# Connections.net
KiCad netlist of a schematic drawn in Altium Designer
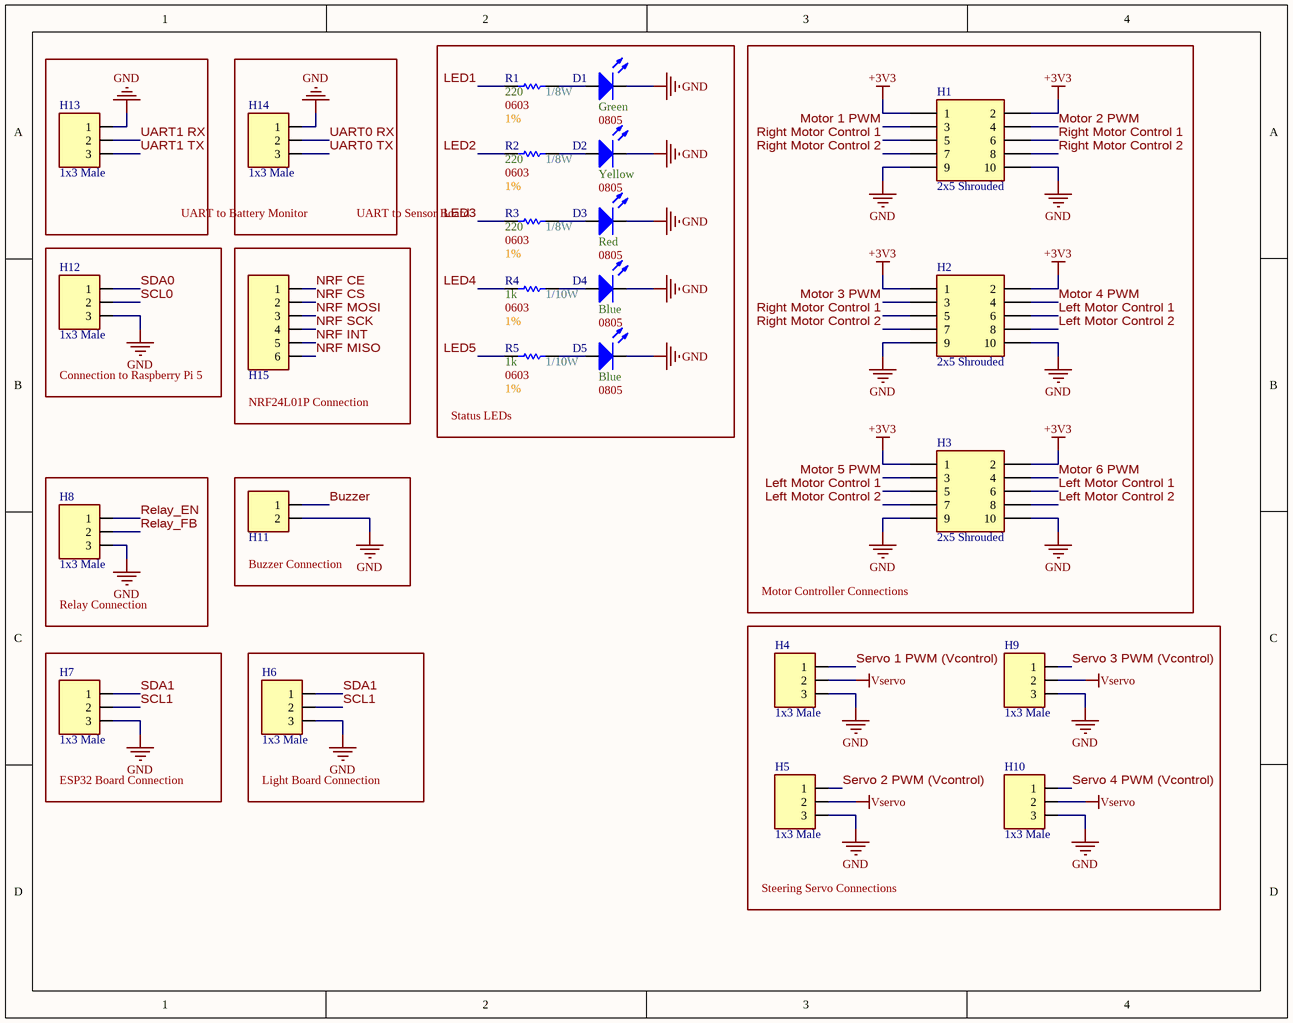
[diagram p0: Connections.SchDoc]

(export (version "E")
  (design (tool "Eeschema 10.0.6"))
  (components
    (comp (ref "D1")
      (value "[LED] SMD 0805 Green")
      (footprint "[LED] SMD 0805")
      (description "LG R971-KN-1-0-20-R18")
      (fields (field (name "COLOR") "Green") (field (name "SIZE PACKAGE") "0805"))
      (libsource (lib "LEDs") (part "[LED] SMD 0805 Green"))
    )
    (comp (ref "D2")
      (value "[LED] SMD 0805 Yellow")
      (footprint "[LED] SMD 0805")
      (description "LY R976-PS-36-0-20-R18")
      (fields (field (name "COLOR") "Yellow") (field (name "SIZE PACKAGE") "0805"))
      (libsource (lib "LEDs") (part "[LED] SMD 0805 Yellow"))
    )
    (comp (ref "D3")
      (value "[LED] SMD 0805 Red")
      (footprint "[LED] SMD 0805")
      (description "LS R976-NR-1-0-20-R18")
      (fields (field (name "COLOR") "Red") (field (name "SIZE PACKAGE") "0805"))
      (libsource (lib "LEDs") (part "[LED] SMD 0805 Red"))
    )
    (comp (ref "D4")
      (value "[LED] SMD 0805 Blue")
      (footprint "[LED] SMD 0805")
      (description "150080BS75000")
      (fields (field (name "COLOR") "Blue") (field (name "SIZE PACKAGE") "0805"))
      (libsource (lib "LEDs") (part "[LED] SMD 0805 Blue"))
    )
    (comp (ref "D5")
      (value "[LED] SMD 0805 Blue")
      (footprint "[LED] SMD 0805")
      (description "150080BS75000")
      (fields (field (name "COLOR") "Blue") (field (name "SIZE PACKAGE") "0805"))
      (libsource (lib "LEDs") (part "[LED] SMD 0805 Blue"))
    )
    (comp (ref "H1")
      (value "2x5 Shrouded")
      (footprint "[Header] Shrouded 2x5 Male")
      (description "BHR-10-VUA")
      (libsource (lib "RADM Connectors") (part "[Header] Shrouded 2x5 Male"))
    )
    (comp (ref "H2")
      (value "2x5 Shrouded")
      (footprint "[Header] Shrouded 2x5 Male")
      (description "BHR-10-VUA")
      (libsource (lib "RADM Connectors") (part "[Header] Shrouded 2x5 Male"))
    )
    (comp (ref "H3")
      (value "2x5 Shrouded")
      (footprint "[Header] Shrouded 2x5 Male")
      (description "BHR-10-VUA")
      (libsource (lib "RADM Connectors") (part "[Header] Shrouded 2x5 Male"))
    )
    (comp (ref "H4")
      (value "1x3 Male")
      (footprint "[Header] Shrouded 1x3 Male")
      (description "070543-0037\r\nMates with 005057-9403")
      (libsource (lib "RADM Connectors") (part "[Header] Shrouded 1x3 Male"))
    )
    (comp (ref "H5")
      (value "1x3 Male")
      (footprint "[Header] Shrouded 1x3 Male")
      (description "070543-0037\r\nMates with 005057-9403")
      (libsource (lib "RADM Connectors") (part "[Header] Shrouded 1x3 Male"))
    )
    (comp (ref "H6")
      (value "1x3 Male")
      (footprint "[Header] Shrouded 1x3 Male")
      (description "070543-0037\r\nMates with 005057-9403")
      (libsource (lib "RADM Connectors") (part "[Header] Shrouded 1x3 Male"))
    )
    (comp (ref "H7")
      (value "1x3 Male")
      (footprint "[Header] Shrouded 1x3 Male")
      (description "070543-0037\r\nMates with 005057-9403")
      (libsource (lib "RADM Connectors") (part "[Header] Shrouded 1x3 Male"))
    )
    (comp (ref "H8")
      (value "1x3 Male")
      (footprint "[Header] Shrouded 1x3 Male")
      (description "070543-0037\r\nMates with 005057-9403")
      (libsource (lib "RADM Connectors") (part "[Header] Shrouded 1x3 Male"))
    )
    (comp (ref "H9")
      (value "1x3 Male")
      (footprint "[Header] Shrouded 1x3 Male")
      (description "070543-0037\r\nMates with 005057-9403")
      (libsource (lib "RADM Connectors") (part "[Header] Shrouded 1x3 Male"))
    )
    (comp (ref "H10")
      (value "1x3 Male")
      (footprint "[Header] Shrouded 1x3 Male")
      (description "070543-0037\r\nMates with 005057-9403")
      (libsource (lib "RADM Connectors") (part "[Header] Shrouded 1x3 Male"))
    )
    (comp (ref "H11")
      (value "1x2 Male")
      (footprint "[Header] Shrouded 1x2 Male")
      (description "0705430036\r\nMates with 0050579402")
      (libsource (lib "RADM Connectors") (part "[Header] Shrouded 1x2 Male"))
    )
    (comp (ref "H12")
      (value "1x3 Male")
      (footprint "[Header] Shrouded 1x3 Male")
      (description "070543-0037\r\nMates with 005057-9403")
      (libsource (lib "RADM Connectors") (part "[Header] Shrouded 1x3 Male"))
    )
    (comp (ref "H13")
      (value "1x3 Male")
      (footprint "[Header] Shrouded 1x3 Male")
      (description "070543-0037\r\nMates with 005057-9403")
      (libsource (lib "RADM Connectors") (part "[Header] Shrouded 1x3 Male"))
    )
    (comp (ref "H14")
      (value "1x3 Male")
      (footprint "[Header] Shrouded 1x3 Male")
      (description "070543-0037\r\nMates with 005057-9403")
      (libsource (lib "RADM Connectors") (part "[Header] Shrouded 1x3 Male"))
    )
    (comp (ref "H15")
      (value "[Header] Shrouded 1x6 Male")
      (footprint "[Header] Shrouded 1x6 Male")
      (description "0705430005\r\nMates with 0050579406")
      (libsource (lib "RADM Connectors") (part "[Header] Shrouded 1x6 Male"))
    )
    (comp (ref "R1")
      (value "[220] SMD 0603 1% 1/10W")
      (footprint "[Res] SMD 0603")
      (description "CRGCQ0805F220R")
      (fields
        (field (name "WATTAGE") "1/8W")
        (field (name "TOLERANCE") "1%")
        (field (name "RESISTANCE") "220")
        (field (name "SIZE PACKAGE") "0603")
      )
      (libsource (lib "Resistors") (part "[220] SMD 0603 1% 1/10W"))
    )
    (comp (ref "R2")
      (value "[220] SMD 0603 1% 1/10W")
      (footprint "[Res] SMD 0603")
      (description "CRGCQ0805F220R")
      (fields
        (field (name "WATTAGE") "1/8W")
        (field (name "TOLERANCE") "1%")
        (field (name "RESISTANCE") "220")
        (field (name "SIZE PACKAGE") "0603")
      )
      (libsource (lib "Resistors") (part "[220] SMD 0603 1% 1/10W"))
    )
    (comp (ref "R3")
      (value "[220] SMD 0603 1% 1/10W")
      (footprint "[Res] SMD 0603")
      (description "CRGCQ0805F220R")
      (fields
        (field (name "WATTAGE") "1/8W")
        (field (name "TOLERANCE") "1%")
        (field (name "RESISTANCE") "220")
        (field (name "SIZE PACKAGE") "0603")
      )
      (libsource (lib "Resistors") (part "[220] SMD 0603 1% 1/10W"))
    )
    (comp (ref "R4")
      (value "[1k] SMD 0603 1% 1/10W")
      (footprint "[Res] SMD 0603")
      (description "RMCF0603FT1K00")
      (fields
        (field (name "WATTAGE") "1/10W")
        (field (name "TOLERANCE") "1%")
        (field (name "RESISTANCE") "1k")
        (field (name "SIZE PACKAGE") "0603")
      )
      (libsource (lib "Resistors") (part "[1k] SMD 0603 1% 1/10W"))
    )
    (comp (ref "R5")
      (value "[1k] SMD 0603 1% 1/10W")
      (footprint "[Res] SMD 0603")
      (description "RMCF0603FT1K00")
      (fields
        (field (name "WATTAGE") "1/10W")
        (field (name "TOLERANCE") "1%")
        (field (name "RESISTANCE") "1k")
        (field (name "SIZE PACKAGE") "0603")
      )
      (libsource (lib "Resistors") (part "[1k] SMD 0603 1% 1/10W"))
    )
  )
  (nets
    (net (code "1") (name "+3V3") (class "Default")
      (node (ref "H1") (pin "1") (pinfunction "1_1") (pintype "passive"))
      (node (ref "H1") (pin "2") (pinfunction "2_2") (pintype "passive"))
      (node (ref "H2") (pin "1") (pinfunction "1_1") (pintype "passive"))
      (node (ref "H2") (pin "2") (pinfunction "2_2") (pintype "passive"))
      (node (ref "H3") (pin "1") (pinfunction "1_1") (pintype "passive"))
      (node (ref "H3") (pin "2") (pinfunction "2_2") (pintype "passive"))
    )
    (net (code "2") (name "/Buzzer") (class "Default")
      (node (ref "H11") (pin "1") (pinfunction "1_1") (pintype "passive"))
    )
    (net (code "3") (name "/LED1") (class "Default")
      (node (ref "R1") (pin "1") (pinfunction "1_1") (pintype "passive"))
    )
    (net (code "4") (name "/LED2") (class "Default")
      (node (ref "R2") (pin "1") (pinfunction "1_1") (pintype "passive"))
    )
    (net (code "5") (name "/LED3") (class "Default")
      (node (ref "R3") (pin "1") (pinfunction "1_1") (pintype "passive"))
    )
    (net (code "6") (name "/LED4") (class "Default")
      (node (ref "R4") (pin "1") (pinfunction "1_1") (pintype "passive"))
    )
    (net (code "7") (name "/LED5") (class "Default")
      (node (ref "R5") (pin "1") (pinfunction "1_1") (pintype "passive"))
    )
    (net (code "8") (name "/Left Motor Control 1") (class "Default")
      (node (ref "H2") (pin "6") (pinfunction "6_6") (pintype "passive"))
      (node (ref "H3") (pin "5") (pinfunction "5_5") (pintype "passive"))
      (node (ref "H3") (pin "6") (pinfunction "6_6") (pintype "passive"))
    )
    (net (code "9") (name "/Left Motor Control 2") (class "Default")
      (node (ref "H2") (pin "8") (pinfunction "8_8") (pintype "passive"))
      (node (ref "H3") (pin "7") (pinfunction "7_7") (pintype "passive"))
      (node (ref "H3") (pin "8") (pinfunction "8_8") (pintype "passive"))
    )
    (net (code "10") (name "/Motor 1 PWM") (class "Default")
      (node (ref "H1") (pin "3") (pinfunction "3_3") (pintype "passive"))
    )
    (net (code "11") (name "/Motor 2 PWM") (class "Default")
      (node (ref "H1") (pin "4") (pinfunction "4_4") (pintype "passive"))
    )
    (net (code "12") (name "/Motor 3 PWM") (class "Default")
      (node (ref "H2") (pin "3") (pinfunction "3_3") (pintype "passive"))
    )
    (net (code "13") (name "/Motor 4 PWM") (class "Default")
      (node (ref "H2") (pin "4") (pinfunction "4_4") (pintype "passive"))
    )
    (net (code "14") (name "/Motor 5 PWM") (class "Default")
      (node (ref "H3") (pin "3") (pinfunction "3_3") (pintype "passive"))
    )
    (net (code "15") (name "/Motor 6 PWM") (class "Default")
      (node (ref "H3") (pin "4") (pinfunction "4_4") (pintype "passive"))
    )
    (net (code "16") (name "/NRF CE") (class "Default")
      (node (ref "H15") (pin "1") (pinfunction "1_1") (pintype "passive"))
    )
    (net (code "17") (name "/NRF CS") (class "Default")
      (node (ref "H15") (pin "2") (pinfunction "2_2") (pintype "passive"))
    )
    (net (code "18") (name "/NRF INT") (class "Default")
      (node (ref "H15") (pin "5") (pinfunction "5_5") (pintype "passive"))
    )
    (net (code "19") (name "/NRF MISO") (class "Default")
      (node (ref "H15") (pin "6") (pinfunction "6_6") (pintype "passive"))
    )
    (net (code "20") (name "/NRF MOSI") (class "Default")
      (node (ref "H15") (pin "3") (pinfunction "3_3") (pintype "passive"))
    )
    (net (code "21") (name "/NRF SCK") (class "Default")
      (node (ref "H15") (pin "4") (pinfunction "4_4") (pintype "passive"))
    )
    (net (code "22") (name "/Relay_EN") (class "Default")
      (node (ref "H8") (pin "1") (pinfunction "1_1") (pintype "passive"))
    )
    (net (code "23") (name "/Relay_FB") (class "Default")
      (node (ref "H8") (pin "2") (pinfunction "2_2") (pintype "passive"))
    )
    (net (code "24") (name "/Right Motor Control 1") (class "Default")
      (node (ref "H1") (pin "5") (pinfunction "5_5") (pintype "passive"))
      (node (ref "H1") (pin "6") (pinfunction "6_6") (pintype "passive"))
      (node (ref "H2") (pin "5") (pinfunction "5_5") (pintype "passive"))
    )
    (net (code "25") (name "/Right Motor Control 2") (class "Default")
      (node (ref "H1") (pin "7") (pinfunction "7_7") (pintype "passive"))
      (node (ref "H1") (pin "8") (pinfunction "8_8") (pintype "passive"))
      (node (ref "H2") (pin "7") (pinfunction "7_7") (pintype "passive"))
    )
    (net (code "26") (name "/SCL0") (class "Default")
      (node (ref "H12") (pin "2") (pinfunction "2_2") (pintype "passive"))
    )
    (net (code "27") (name "/SCL1") (class "Default")
      (node (ref "H6") (pin "2") (pinfunction "2_2") (pintype "passive"))
      (node (ref "H7") (pin "2") (pinfunction "2_2") (pintype "passive"))
    )
    (net (code "28") (name "/SDA0") (class "Default")
      (node (ref "H12") (pin "1") (pinfunction "1_1") (pintype "passive"))
    )
    (net (code "29") (name "/SDA1") (class "Default")
      (node (ref "H6") (pin "1") (pinfunction "1_1") (pintype "passive"))
      (node (ref "H7") (pin "1") (pinfunction "1_1") (pintype "passive"))
    )
    (net (code "30") (name "/Servo 1 PWM (Vcontrol)") (class "Default")
      (node (ref "H4") (pin "1") (pinfunction "1_1") (pintype "passive"))
    )
    (net (code "31") (name "/Servo 2 PWM (Vcontrol)") (class "Default")
      (node (ref "H5") (pin "1") (pinfunction "1_1") (pintype "passive"))
    )
    (net (code "32") (name "/Servo 3 PWM (Vcontrol)") (class "Default")
      (node (ref "H9") (pin "1") (pinfunction "1_1") (pintype "passive"))
    )
    (net (code "33") (name "/Servo 4 PWM (Vcontrol)") (class "Default")
      (node (ref "H10") (pin "1") (pinfunction "1_1") (pintype "passive"))
    )
    (net (code "34") (name "/UART0 RX") (class "Default")
      (node (ref "H14") (pin "2") (pinfunction "2_2") (pintype "passive"))
    )
    (net (code "35") (name "/UART0 TX") (class "Default")
      (node (ref "H14") (pin "3") (pinfunction "3_3") (pintype "passive"))
    )
    (net (code "36") (name "/UART1 RX") (class "Default")
      (node (ref "H13") (pin "2") (pinfunction "2_2") (pintype "passive"))
    )
    (net (code "37") (name "/UART1 TX") (class "Default")
      (node (ref "H13") (pin "3") (pinfunction "3_3") (pintype "passive"))
    )
    (net (code "38") (name "GND") (class "Default")
      (node (ref "D1") (pin "2") (pinfunction "Cathode_2") (pintype "passive"))
      (node (ref "D2") (pin "2") (pinfunction "Cathode_2") (pintype "passive"))
      (node (ref "D3") (pin "2") (pinfunction "Cathode_2") (pintype "passive"))
      (node (ref "D4") (pin "2") (pinfunction "Cathode_2") (pintype "passive"))
      (node (ref "D5") (pin "2") (pinfunction "Cathode_2") (pintype "passive"))
      (node (ref "H1") (pin "10") (pinfunction "10_10") (pintype "passive"))
      (node (ref "H1") (pin "9") (pinfunction "9_9") (pintype "passive"))
      (node (ref "H10") (pin "3") (pinfunction "3_3") (pintype "passive"))
      (node (ref "H11") (pin "2") (pinfunction "2_2") (pintype "passive"))
      (node (ref "H12") (pin "3") (pinfunction "3_3") (pintype "passive"))
      (node (ref "H13") (pin "1") (pinfunction "1_1") (pintype "passive"))
      (node (ref "H14") (pin "1") (pinfunction "1_1") (pintype "passive"))
      (node (ref "H2") (pin "10") (pinfunction "10_10") (pintype "passive"))
      (node (ref "H2") (pin "9") (pinfunction "9_9") (pintype "passive"))
      (node (ref "H3") (pin "10") (pinfunction "10_10") (pintype "passive"))
      (node (ref "H3") (pin "9") (pinfunction "9_9") (pintype "passive"))
      (node (ref "H4") (pin "3") (pinfunction "3_3") (pintype "passive"))
      (node (ref "H5") (pin "3") (pinfunction "3_3") (pintype "passive"))
      (node (ref "H6") (pin "3") (pinfunction "3_3") (pintype "passive"))
      (node (ref "H7") (pin "3") (pinfunction "3_3") (pintype "passive"))
      (node (ref "H8") (pin "3") (pinfunction "3_3") (pintype "passive"))
      (node (ref "H9") (pin "3") (pinfunction "3_3") (pintype "passive"))
    )
    (net (code "39") (name "Net-(D1-Anode)") (class "Default")
      (node (ref "D1") (pin "1") (pinfunction "Anode_1") (pintype "passive"))
      (node (ref "R1") (pin "2") (pinfunction "2_2") (pintype "passive"))
    )
    (net (code "40") (name "Net-(D2-Anode)") (class "Default")
      (node (ref "D2") (pin "1") (pinfunction "Anode_1") (pintype "passive"))
      (node (ref "R2") (pin "2") (pinfunction "2_2") (pintype "passive"))
    )
    (net (code "41") (name "Net-(D3-Anode)") (class "Default")
      (node (ref "D3") (pin "1") (pinfunction "Anode_1") (pintype "passive"))
      (node (ref "R3") (pin "2") (pinfunction "2_2") (pintype "passive"))
    )
    (net (code "42") (name "Net-(D4-Anode)") (class "Default")
      (node (ref "D4") (pin "1") (pinfunction "Anode_1") (pintype "passive"))
      (node (ref "R4") (pin "2") (pinfunction "2_2") (pintype "passive"))
    )
    (net (code "43") (name "Net-(D5-Anode)") (class "Default")
      (node (ref "D5") (pin "1") (pinfunction "Anode_1") (pintype "passive"))
      (node (ref "R5") (pin "2") (pinfunction "2_2") (pintype "passive"))
    )
    (net (code "44") (name "Vservo") (class "Default")
      (node (ref "H10") (pin "2") (pinfunction "2_2") (pintype "passive"))
      (node (ref "H4") (pin "2") (pinfunction "2_2") (pintype "passive"))
      (node (ref "H5") (pin "2") (pinfunction "2_2") (pintype "passive"))
      (node (ref "H9") (pin "2") (pinfunction "2_2") (pintype "passive"))
    )
  )
)
